# main.net
KiCad netlist of a schematic drawn in Altium Designer
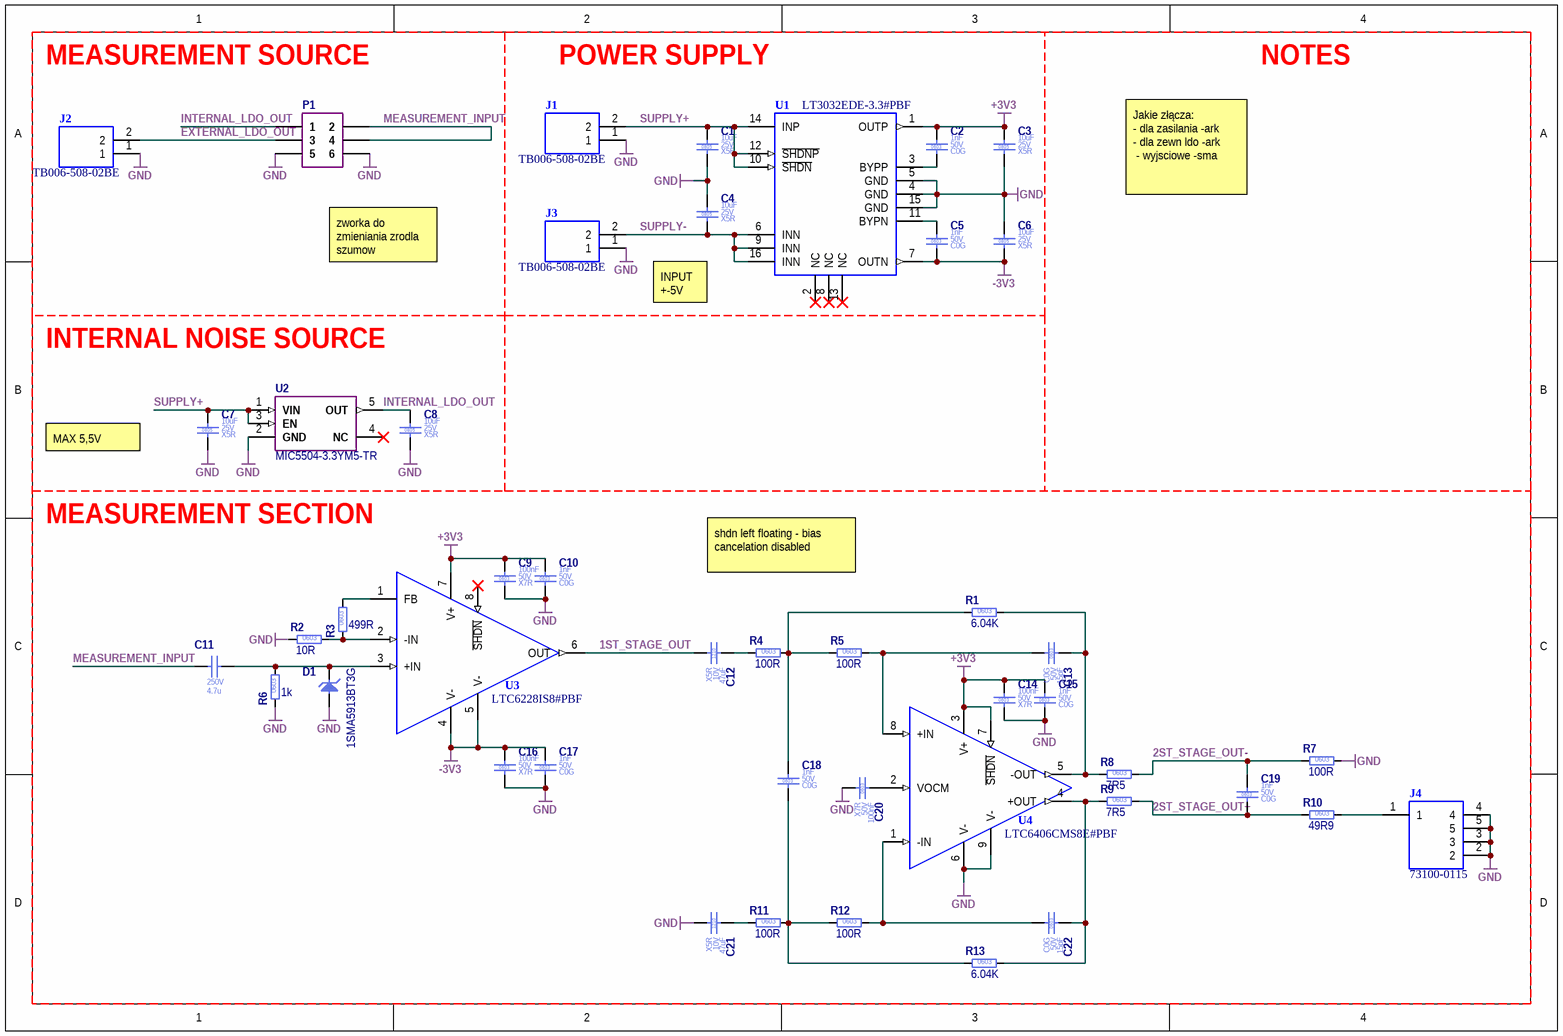
[diagram p0: main.SchDoc]

(export (version "E")
  (design (tool "Eeschema 10.0.6"))
  (components
    (comp (ref "C1")
      (value "C_10UF_25V_X5R_0805_20")
      (footprint "C_0805_2012")
      (description "Ceramic Capacitor")
      (fields
        (field (name "CASE/PACKAGE") "0805")
        (field (name "VOLTAGE RATING (DC)") "25V")
        (field (name "DIELECTRIC") "X5R")
        (field (name "CAPACITANCE") "10uF")
        (field (name "TOLERANCE") "20%")
        (field (name "MANUFACTURER PART NUMBER") "TMK212BBJ106MG-T")
      )
      (libsource (lib "7Sigma") (part "C"))
    )
    (comp (ref "C2")
      (value "C_1NF_50V_C0G_0603_5")
      (footprint "C_0603_1608")
      (description "Ceramic Capacitor")
      (fields
        (field (name "CASE/PACKAGE") "0603")
        (field (name "VOLTAGE RATING (DC)") "50V")
        (field (name "DIELECTRIC") "C0G")
        (field (name "CAPACITANCE") "1nF")
        (field (name "TOLERANCE") "10%")
      )
      (libsource (lib "7Sigma") (part "C"))
    )
    (comp (ref "C3")
      (value "C_10UF_25V_X5R_0805_20")
      (footprint "C_0805_2012")
      (description "Ceramic Capacitor")
      (fields
        (field (name "CASE/PACKAGE") "0805")
        (field (name "VOLTAGE RATING (DC)") "25V")
        (field (name "DIELECTRIC") "X5R")
        (field (name "CAPACITANCE") "10uF")
        (field (name "TOLERANCE") "20%")
        (field (name "MANUFACTURER PART NUMBER") "TMK212BBJ106MG-T")
      )
      (libsource (lib "7Sigma") (part "C"))
    )
    (comp (ref "C4")
      (value "C_10UF_25V_X5R_0805_20")
      (footprint "C_0805_2012")
      (description "Ceramic Capacitor")
      (fields
        (field (name "CASE/PACKAGE") "0805")
        (field (name "VOLTAGE RATING (DC)") "25V")
        (field (name "DIELECTRIC") "X5R")
        (field (name "CAPACITANCE") "10uF")
        (field (name "TOLERANCE") "20%")
        (field (name "MANUFACTURER PART NUMBER") "TMK212BBJ106MG-T")
      )
      (libsource (lib "7Sigma") (part "C"))
    )
    (comp (ref "C5")
      (value "C_1NF_50V_C0G_0603_5")
      (footprint "C_0603_1608")
      (description "Ceramic Capacitor")
      (fields
        (field (name "CASE/PACKAGE") "0603")
        (field (name "VOLTAGE RATING (DC)") "50V")
        (field (name "DIELECTRIC") "C0G")
        (field (name "CAPACITANCE") "1nF")
        (field (name "TOLERANCE") "10%")
      )
      (libsource (lib "7Sigma") (part "C"))
    )
    (comp (ref "C6")
      (value "C_10UF_25V_X5R_0805_20")
      (footprint "C_0805_2012")
      (description "Ceramic Capacitor")
      (fields
        (field (name "CASE/PACKAGE") "0805")
        (field (name "VOLTAGE RATING (DC)") "25V")
        (field (name "DIELECTRIC") "X5R")
        (field (name "CAPACITANCE") "10uF")
        (field (name "TOLERANCE") "20%")
        (field (name "MANUFACTURER PART NUMBER") "TMK212BBJ106MG-T")
      )
      (libsource (lib "7Sigma") (part "C"))
    )
    (comp (ref "C7")
      (value "C_10UF_25V_X5R_0805_20")
      (footprint "C_0805_2012")
      (description "Ceramic Capacitor")
      (fields
        (field (name "CASE/PACKAGE") "0805")
        (field (name "VOLTAGE RATING (DC)") "25V")
        (field (name "DIELECTRIC") "X5R")
        (field (name "CAPACITANCE") "10uF")
        (field (name "TOLERANCE") "20%")
        (field (name "MANUFACTURER PART NUMBER") "TMK212BBJ106MG-T")
      )
      (libsource (lib "7Sigma") (part "C"))
    )
    (comp (ref "C8")
      (value "C_10UF_25V_X5R_0805_20")
      (footprint "C_0805_2012")
      (description "Ceramic Capacitor")
      (fields
        (field (name "CASE/PACKAGE") "0805")
        (field (name "VOLTAGE RATING (DC)") "25V")
        (field (name "DIELECTRIC") "X5R")
        (field (name "CAPACITANCE") "10uF")
        (field (name "TOLERANCE") "20%")
        (field (name "MANUFACTURER PART NUMBER") "TMK212BBJ106MG-T")
      )
      (libsource (lib "7Sigma") (part "C"))
    )
    (comp (ref "C9")
      (value "C_100NF_50V_X7R_0603_5")
      (footprint "C_0603_1608")
      (description "Ceramic Capacitor")
      (fields
        (field (name "CASE/PACKAGE") "0603")
        (field (name "VOLTAGE RATING (DC)") "50V")
        (field (name "DIELECTRIC") "X7R")
        (field (name "CAPACITANCE") "100nF")
        (field (name "TOLERANCE") "5%")
        (field (name "MANUFACTURER PART NUMBER") "CC0603JRX7R9BB104")
      )
      (libsource (lib "7Sigma") (part "C"))
    )
    (comp (ref "C10")
      (value "C_1NF_50V_C0G_0603_5")
      (footprint "C_0603_1608")
      (description "Ceramic Capacitor")
      (fields
        (field (name "CASE/PACKAGE") "0603")
        (field (name "VOLTAGE RATING (DC)") "50V")
        (field (name "DIELECTRIC") "C0G")
        (field (name "CAPACITANCE") "1nF")
        (field (name "TOLERANCE") "10%")
      )
      (libsource (lib "7Sigma") (part "C"))
    )
    (comp (ref "C11")
      (value "C")
      (footprint "CP_22.5mm_tht")
      (description "Film Capacitors 250VDC 4.7uF 10% MPET L/S=22.5mm")
      (fields (field (name "VOLTAGE RATING (DC)") "250V") (field (name "CAPACITANCE") "4.7u"))
      (libsource (lib "SamacSys") (part "CP_4U7_250V_22.5mm_10"))
    )
    (comp (ref "C12")
      (value "C_47UF_10V_X5R_1210_10")
      (footprint "C_1210_3225")
      (description "Ceramic Capacitor")
      (fields
        (field (name "CASE/PACKAGE") "1210")
        (field (name "VOLTAGE RATING (DC)") "10V")
        (field (name "DIELECTRIC") "X5R")
        (field (name "CAPACITANCE") "47uF")
        (field (name "TOLERANCE") "10%")
      )
      (libsource (lib "7Sigma") (part "C"))
    )
    (comp (ref "C13")
      (value "C_15PF_50V_C0G_0603_5")
      (footprint "C_0603_1608")
      (description "Ceramic Capacitor")
      (fields
        (field (name "CASE/PACKAGE") "0603")
        (field (name "VOLTAGE RATING (DC)") "50V")
        (field (name "DIELECTRIC") "C0G")
        (field (name "CAPACITANCE") "15pF")
        (field (name "TOLERANCE") "10%")
      )
      (libsource (lib "7Sigma") (part "C"))
    )
    (comp (ref "C14")
      (value "C_100NF_50V_X7R_0603_5")
      (footprint "C_0603_1608")
      (description "Ceramic Capacitor")
      (fields
        (field (name "CASE/PACKAGE") "0603")
        (field (name "VOLTAGE RATING (DC)") "50V")
        (field (name "DIELECTRIC") "X7R")
        (field (name "CAPACITANCE") "100nF")
        (field (name "TOLERANCE") "5%")
        (field (name "MANUFACTURER PART NUMBER") "CC0603JRX7R9BB104")
      )
      (libsource (lib "7Sigma") (part "C"))
    )
    (comp (ref "C15")
      (value "C_1NF_50V_C0G_0603_5")
      (footprint "C_0603_1608")
      (description "Ceramic Capacitor")
      (fields
        (field (name "CASE/PACKAGE") "0603")
        (field (name "VOLTAGE RATING (DC)") "50V")
        (field (name "DIELECTRIC") "C0G")
        (field (name "CAPACITANCE") "1nF")
        (field (name "TOLERANCE") "10%")
      )
      (libsource (lib "7Sigma") (part "C"))
    )
    (comp (ref "C16")
      (value "C_100NF_50V_X7R_0603_5")
      (footprint "C_0603_1608")
      (description "Ceramic Capacitor")
      (fields
        (field (name "CASE/PACKAGE") "0603")
        (field (name "VOLTAGE RATING (DC)") "50V")
        (field (name "DIELECTRIC") "X7R")
        (field (name "CAPACITANCE") "100nF")
        (field (name "TOLERANCE") "5%")
        (field (name "MANUFACTURER PART NUMBER") "CC0603JRX7R9BB104")
      )
      (libsource (lib "7Sigma") (part "C"))
    )
    (comp (ref "C17")
      (value "C_1NF_50V_C0G_0603_5")
      (footprint "C_0603_1608")
      (description "Ceramic Capacitor")
      (fields
        (field (name "CASE/PACKAGE") "0603")
        (field (name "VOLTAGE RATING (DC)") "50V")
        (field (name "DIELECTRIC") "C0G")
        (field (name "CAPACITANCE") "1nF")
        (field (name "TOLERANCE") "10%")
      )
      (libsource (lib "7Sigma") (part "C"))
    )
    (comp (ref "C18")
      (value "C_1NF_50V_C0G_0603_5")
      (footprint "C_0603_1608")
      (description "Ceramic Capacitor")
      (fields
        (field (name "CASE/PACKAGE") "0603")
        (field (name "VOLTAGE RATING (DC)") "50V")
        (field (name "DIELECTRIC") "C0G")
        (field (name "CAPACITANCE") "1nF")
        (field (name "TOLERANCE") "10%")
      )
      (libsource (lib "7Sigma") (part "C"))
    )
    (comp (ref "C19")
      (value "C_1NF_50V_C0G_0603_5")
      (footprint "C_0603_1608")
      (description "Ceramic Capacitor")
      (fields
        (field (name "CASE/PACKAGE") "0603")
        (field (name "VOLTAGE RATING (DC)") "50V")
        (field (name "DIELECTRIC") "C0G")
        (field (name "CAPACITANCE") "1nF")
        (field (name "TOLERANCE") "10%")
      )
      (libsource (lib "7Sigma") (part "C"))
    )
    (comp (ref "C20")
      (value "C_100NF_50V_X7R_0603_5")
      (footprint "C_0603_1608")
      (description "Ceramic Capacitor")
      (fields
        (field (name "CASE/PACKAGE") "0603")
        (field (name "VOLTAGE RATING (DC)") "50V")
        (field (name "DIELECTRIC") "X7R")
        (field (name "CAPACITANCE") "100nF")
        (field (name "TOLERANCE") "5%")
        (field (name "MANUFACTURER PART NUMBER") "CC0603JRX7R9BB104")
      )
      (libsource (lib "7Sigma") (part "C"))
    )
    (comp (ref "C21")
      (value "C_47UF_10V_X5R_1210_10")
      (footprint "C_1210_3225")
      (description "Ceramic Capacitor")
      (fields
        (field (name "CASE/PACKAGE") "1210")
        (field (name "VOLTAGE RATING (DC)") "10V")
        (field (name "DIELECTRIC") "X5R")
        (field (name "CAPACITANCE") "47uF")
        (field (name "TOLERANCE") "10%")
      )
      (libsource (lib "7Sigma") (part "C"))
    )
    (comp (ref "C22")
      (value "C_15PF_50V_C0G_0603_5")
      (footprint "C_0603_1608")
      (description "Ceramic Capacitor")
      (fields
        (field (name "CASE/PACKAGE") "0603")
        (field (name "VOLTAGE RATING (DC)") "50V")
        (field (name "DIELECTRIC") "C0G")
        (field (name "CAPACITANCE") "15pF")
        (field (name "TOLERANCE") "10%")
      )
      (libsource (lib "7Sigma") (part "C"))
    )
    (comp (ref "D1")
      (value "1SMA5913BT3G")
      (footprint "SMA-2")
      (description "Zener Diodes 3.3V 1.5W")
      (libsource (lib "SamacSys") (part "1SMA5913BT3G"))
    )
    (comp (ref "J1")
      (value "TB006-508-02BE")
      (footprint "SamacSys:TB00650802BE")
      (fields (field (name "MOUSER PART NUMBER") "490-TB006-508-02BE"))
      (libsource (lib "SamacSys") (part "TB006-508-02BE"))
    )
    (comp (ref "J2")
      (value "TB006-508-02BE")
      (footprint "SamacSys:TB00650802BE")
      (fields (field (name "MOUSER PART NUMBER") "490-TB006-508-02BE"))
      (libsource (lib "SamacSys") (part "TB006-508-02BE"))
    )
    (comp (ref "J3")
      (value "TB006-508-02BE")
      (footprint "SamacSys:TB00650802BE")
      (fields (field (name "MOUSER PART NUMBER") "490-TB006-508-02BE"))
      (libsource (lib "SamacSys") (part "TB006-508-02BE"))
    )
    (comp (ref "J4")
      (value "73100-0115")
      (footprint "SamacSys:731000115")
      (description "SMA right angle connector female")
      (fields (field (name "MOUSER PART NUMBER") "538-73100-0115"))
      (libsource (lib "SamacSys") (part "73100-0115"))
    )
    (comp (ref "P1")
      (value "826925-3")
      (footprint "HEADER_M_2x3_2.54")
      (description "Header, 3-Pin, Dual row")
      (fields (field (name "MANUFACTURER") "TE Connectivity"))
      (libsource (lib "7Sigma") (part "HEADER_2x3"))
    )
    (comp (ref "R1")
      (value "R_6K04_0603_1")
      (footprint "R_0603_1608")
      (description "Thin Film Resistor")
      (fields
        (field (name "RESISTANCE") "6.04K")
        (field (name "CASE/PACKAGE") "0603")
        (field (name "TOLERANCE") "1%")
        (field (name "MANUFACTURER") "Yageo")
      )
      (libsource (lib "7Sigma") (part "R"))
    )
    (comp (ref "R2")
      (value "R_10R_0603_1")
      (footprint "R_0603_1608")
      (fields
        (field (name "RESISTANCE") "10R")
        (field (name "CASE/PACKAGE") "0603")
        (field (name "TOLERANCE") "1%")
      )
      (libsource (lib "7Sigma") (part "R"))
    )
    (comp (ref "R3")
      (value "R_499R_0603_1")
      (footprint "R_0603_1608")
      (description "Thin Film Resistors")
      (fields
        (field (name "RESISTANCE") "499R")
        (field (name "CASE/PACKAGE") "0603")
        (field (name "TOLERANCE") "1%")
        (field (name "MANUFACTURER") "Yageo")
      )
      (libsource (lib "7Sigma") (part "R"))
    )
    (comp (ref "R4")
      (value "R_100R_0603_1")
      (footprint "R_0603_1608")
      (fields
        (field (name "RESISTANCE") "100R")
        (field (name "CASE/PACKAGE") "0603")
        (field (name "TOLERANCE") "1%")
      )
      (libsource (lib "7Sigma") (part "R"))
    )
    (comp (ref "R5")
      (value "R_100R_0603_1")
      (footprint "R_0603_1608")
      (fields
        (field (name "RESISTANCE") "100R")
        (field (name "CASE/PACKAGE") "0603")
        (field (name "TOLERANCE") "1%")
      )
      (libsource (lib "7Sigma") (part "R"))
    )
    (comp (ref "R6")
      (value "R_1K_0603_1")
      (footprint "R_0603_1608")
      (fields
        (field (name "RESISTANCE") "1k")
        (field (name "CASE/PACKAGE") "0603")
        (field (name "TOLERANCE") "1%")
      )
      (libsource (lib "7Sigma") (part "R"))
    )
    (comp (ref "R7")
      (value "R_100R_0603_1")
      (footprint "R_0603_1608")
      (fields
        (field (name "RESISTANCE") "100R")
        (field (name "CASE/PACKAGE") "0603")
        (field (name "TOLERANCE") "1%")
      )
      (libsource (lib "7Sigma") (part "R"))
    )
    (comp (ref "R8")
      (value "R_7R5_0603_1")
      (footprint "R_0603_1608")
      (description "Thin Film Resistor")
      (fields
        (field (name "RESISTANCE") "7R5")
        (field (name "CASE/PACKAGE") "0603")
        (field (name "TOLERANCE") "1%")
        (field (name "MANUFACTURER") "Yageo")
      )
      (libsource (lib "7Sigma") (part "R"))
    )
    (comp (ref "R9")
      (value "R_7R5_0603_1")
      (footprint "R_0603_1608")
      (description "Thin Film Resistor")
      (fields
        (field (name "RESISTANCE") "7R5")
        (field (name "CASE/PACKAGE") "0603")
        (field (name "TOLERANCE") "1%")
        (field (name "MANUFACTURER") "Yageo")
      )
      (libsource (lib "7Sigma") (part "R"))
    )
    (comp (ref "R10")
      (value "R_49R9_0603_1")
      (footprint "R_0603_1608")
      (description "Thin Film Resistors")
      (fields
        (field (name "RESISTANCE") "49R9")
        (field (name "CASE/PACKAGE") "0603")
        (field (name "TOLERANCE") "1%")
        (field (name "MANUFACTURER") "Yageo")
      )
      (libsource (lib "7Sigma") (part "R"))
    )
    (comp (ref "R11")
      (value "R_100R_0603_1")
      (footprint "R_0603_1608")
      (fields
        (field (name "RESISTANCE") "100R")
        (field (name "CASE/PACKAGE") "0603")
        (field (name "TOLERANCE") "1%")
      )
      (libsource (lib "7Sigma") (part "R"))
    )
    (comp (ref "R12")
      (value "R_100R_0603_1")
      (footprint "R_0603_1608")
      (fields
        (field (name "RESISTANCE") "100R")
        (field (name "CASE/PACKAGE") "0603")
        (field (name "TOLERANCE") "1%")
      )
      (libsource (lib "7Sigma") (part "R"))
    )
    (comp (ref "R13")
      (value "R_6K04_0603_1")
      (footprint "R_0603_1608")
      (description "Thin Film Resistor")
      (fields
        (field (name "RESISTANCE") "6.04K")
        (field (name "CASE/PACKAGE") "0603")
        (field (name "TOLERANCE") "1%")
        (field (name "MANUFACTURER") "Yageo")
      )
      (libsource (lib "7Sigma") (part "R"))
    )
    (comp (ref "U1")
      (value "LT3032EDE-3.3#PBF")
      (footprint "SamacSys:LT3032EDE5PBF")
      (fields (field (name "MOUSER PART NUMBER") "584-LT3032EDE-3.3PBF"))
      (libsource (lib "SamacSys") (part "LT3032EDE-5#PBF"))
    )
    (comp (ref "U2")
      (value "MIC5504-3.3YM5-TR")
      (footprint "SOT23-5_SC74A_SOT753_M")
      (description "LDO Voltage Regulators Single 300mA LDO")
      (fields (field (name "MANUFACTURER") "Microchip"))
      (libsource (lib "7Sigma") (part "MIC5504-3.3YM5-TR"))
    )
    (comp (ref "U3")
      (value "LTC6228IS8#PBF")
      (footprint "SamacSys:SOIC127P599X175-8N")
      (description "High Speed Operational Amplifiers Precision Low Drift & Noise HiSpeed")
      (fields (field (name "MOUSER PART NUMBER") "584-LTC6228IS8#PBF"))
      (libsource (lib "SamacSys") (part "LTC6228IS8#PBF"))
    )
    (comp (ref "U4")
      (value "LTC6406CMS8E#PBF")
      (footprint "SamacSys:SOP65P490X110-9N")
      (fields (field (name "MOUSER PART NUMBER") "584-LTC6406CMS8E#PBF"))
      (libsource (lib "SamacSys") (part "LTC6406CMS8E#PBF"))
    )
  )
  (nets
    (net (code "1") (name "+3V3") (class "Default")
      (node (ref "C10") (pin "1") (pinfunction "1_1") (pintype "passive"))
      (node (ref "C14") (pin "1") (pinfunction "1_1") (pintype "passive"))
      (node (ref "C15") (pin "1") (pinfunction "1_1") (pintype "passive"))
      (node (ref "C2") (pin "1") (pinfunction "1_1") (pintype "passive"))
      (node (ref "C3") (pin "1") (pinfunction "1_1") (pintype "passive"))
      (node (ref "C9") (pin "1") (pinfunction "1_1") (pintype "passive"))
      (node (ref "U1") (pin "1") (pinfunction "OUTP_1") (pintype "output"))
      (node (ref "U3") (pin "7") (pinfunction "V+_7") (pintype "power_in"))
      (node (ref "U4") (pin "3") (pinfunction "V+_3") (pintype "power_in"))
      (node (ref "U4") (pin "7") (pinfunction "~{SHDN}_7") (pintype "input"))
    )
    (net (code "2") (name "-3V3") (class "Default")
      (node (ref "C16") (pin "1") (pinfunction "1_1") (pintype "passive"))
      (node (ref "C17") (pin "1") (pinfunction "1_1") (pintype "passive"))
      (node (ref "C5") (pin "2") (pinfunction "2_2") (pintype "passive"))
      (node (ref "C6") (pin "2") (pinfunction "2_2") (pintype "passive"))
      (node (ref "U1") (pin "7") (pinfunction "OUTN_7") (pintype "output"))
      (node (ref "U3") (pin "4") (pinfunction "V-_4") (pintype "power_in"))
      (node (ref "U3") (pin "5") (pinfunction "V-_5") (pintype "power_in"))
    )
    (net (code "3") (name "/1ST_STAGE_OUT") (class "Default")
      (node (ref "C12") (pin "2") (pinfunction "2_2") (pintype "passive"))
      (node (ref "U3") (pin "6") (pinfunction "OUT_6") (pintype "output"))
    )
    (net (code "4") (name "/2ST_STAGE_OUT+") (class "Default")
      (node (ref "C19") (pin "2") (pinfunction "2_2") (pintype "passive"))
      (node (ref "R10") (pin "1") (pinfunction "1_1") (pintype "passive"))
      (node (ref "R9") (pin "2") (pinfunction "2_2") (pintype "passive"))
    )
    (net (code "5") (name "/2ST_STAGE_OUT-") (class "Default")
      (node (ref "C19") (pin "1") (pinfunction "1_1") (pintype "passive"))
      (node (ref "R7") (pin "1") (pinfunction "1_1") (pintype "passive"))
      (node (ref "R8") (pin "2") (pinfunction "2_2") (pintype "passive"))
    )
    (net (code "6") (name "/EXTERNAL_LDO_OUT") (class "Default")
      (node (ref "J2") (pin "2") (pinfunction "2_2") (pintype "passive"))
      (node (ref "P1") (pin "3") (pinfunction "3_3") (pintype "passive"))
    )
    (net (code "7") (name "/INTERNAL_LDO_OUT") (class "Default")
      (node (ref "C8") (pin "1") (pinfunction "1_1") (pintype "passive"))
      (node (ref "P1") (pin "1") (pinfunction "1_1") (pintype "passive"))
      (node (ref "U2") (pin "5") (pinfunction "OUT_5") (pintype "output"))
    )
    (net (code "8") (name "/MEASUREMENT_INPUT") (class "Default")
      (node (ref "C11") (pin "2") (pinfunction "2_2") (pintype "passive"))
      (node (ref "P1") (pin "2") (pinfunction "2_2") (pintype "passive"))
      (node (ref "P1") (pin "4") (pinfunction "4_4") (pintype "passive"))
    )
    (net (code "9") (name "/SUPPLY+") (class "Default")
      (node (ref "C1") (pin "1") (pinfunction "1_1") (pintype "passive"))
      (node (ref "C7") (pin "1") (pinfunction "1_1") (pintype "passive"))
      (node (ref "J1") (pin "2") (pinfunction "2_2") (pintype "passive"))
      (node (ref "U1") (pin "10") (pinfunction "~{SHDN}_10") (pintype "input"))
      (node (ref "U1") (pin "12") (pinfunction "~{SHDNP}_12") (pintype "input"))
      (node (ref "U1") (pin "14") (pinfunction "INP_14") (pintype "power_in"))
      (node (ref "U2") (pin "1") (pinfunction "VIN_1") (pintype "input"))
      (node (ref "U2") (pin "3") (pinfunction "EN_3") (pintype "input"))
    )
    (net (code "10") (name "/SUPPLY-") (class "Default")
      (node (ref "C4") (pin "2") (pinfunction "2_2") (pintype "passive"))
      (node (ref "J3") (pin "2") (pinfunction "2_2") (pintype "passive"))
      (node (ref "U1") (pin "16") (pinfunction "INN_16") (pintype "power_in"))
      (node (ref "U1") (pin "6") (pinfunction "INN_6") (pintype "power_in"))
      (node (ref "U1") (pin "9") (pinfunction "INN_9") (pintype "power_in"))
    )
    (net (code "11") (name "GND") (class "Default")
      (node (ref "C1") (pin "2") (pinfunction "2_2") (pintype "passive"))
      (node (ref "C10") (pin "2") (pinfunction "2_2") (pintype "passive"))
      (node (ref "C14") (pin "2") (pinfunction "2_2") (pintype "passive"))
      (node (ref "C15") (pin "2") (pinfunction "2_2") (pintype "passive"))
      (node (ref "C16") (pin "2") (pinfunction "2_2") (pintype "passive"))
      (node (ref "C17") (pin "2") (pinfunction "2_2") (pintype "passive"))
      (node (ref "C20") (pin "2") (pinfunction "2_2") (pintype "passive"))
      (node (ref "C21") (pin "2") (pinfunction "2_2") (pintype "passive"))
      (node (ref "C3") (pin "2") (pinfunction "2_2") (pintype "passive"))
      (node (ref "C4") (pin "1") (pinfunction "1_1") (pintype "passive"))
      (node (ref "C6") (pin "1") (pinfunction "1_1") (pintype "passive"))
      (node (ref "C7") (pin "2") (pinfunction "2_2") (pintype "passive"))
      (node (ref "C8") (pin "2") (pinfunction "2_2") (pintype "passive"))
      (node (ref "C9") (pin "2") (pinfunction "2_2") (pintype "passive"))
      (node (ref "D1") (pin "1") (pinfunction "A_1") (pintype "passive"))
      (node (ref "J1") (pin "1") (pinfunction "1_1") (pintype "passive"))
      (node (ref "J2") (pin "1") (pinfunction "1_1") (pintype "passive"))
      (node (ref "J3") (pin "1") (pinfunction "1_1") (pintype "passive"))
      (node (ref "J4") (pin "2") (pinfunction "2_2") (pintype "passive"))
      (node (ref "J4") (pin "3") (pinfunction "3_3") (pintype "passive"))
      (node (ref "J4") (pin "4") (pinfunction "4_4") (pintype "passive"))
      (node (ref "J4") (pin "5") (pinfunction "5_5") (pintype "passive"))
      (node (ref "P1") (pin "5") (pinfunction "5_5") (pintype "passive"))
      (node (ref "P1") (pin "6") (pinfunction "6_6") (pintype "passive"))
      (node (ref "R2") (pin "1") (pinfunction "1_1") (pintype "passive"))
      (node (ref "R6") (pin "1") (pinfunction "1_1") (pintype "passive"))
      (node (ref "R7") (pin "2") (pinfunction "2_2") (pintype "passive"))
      (node (ref "U1") (pin "15") (pinfunction "GND_15") (pintype "power_in"))
      (node (ref "U1") (pin "4") (pinfunction "GND_4") (pintype "power_in"))
      (node (ref "U1") (pin "5") (pinfunction "GND_5") (pintype "power_in"))
      (node (ref "U2") (pin "2") (pinfunction "GND_2") (pintype "power_in"))
      (node (ref "U4") (pin "6") (pinfunction "V-_6") (pintype "power_in"))
      (node (ref "U4") (pin "9") (pinfunction "V-_9") (pintype "power_in"))
    )
    (net (code "12") (name "Net-(C12-Pad1)") (class "Default")
      (node (ref "C12") (pin "1") (pinfunction "1_1") (pintype "passive"))
      (node (ref "R4") (pin "1") (pinfunction "1_1") (pintype "passive"))
    )
    (net (code "13") (name "Net-(C18-Pad1)") (class "Default")
      (node (ref "C18") (pin "1") (pinfunction "1_1") (pintype "passive"))
      (node (ref "R1") (pin "1") (pinfunction "1_1") (pintype "passive"))
      (node (ref "R4") (pin "2") (pinfunction "2_2") (pintype "passive"))
      (node (ref "R5") (pin "1") (pinfunction "1_1") (pintype "passive"))
    )
    (net (code "14") (name "Net-(C18-Pad2)") (class "Default")
      (node (ref "C18") (pin "2") (pinfunction "2_2") (pintype "passive"))
      (node (ref "R11") (pin "2") (pinfunction "2_2") (pintype "passive"))
      (node (ref "R12") (pin "1") (pinfunction "1_1") (pintype "passive"))
      (node (ref "R13") (pin "1") (pinfunction "1_1") (pintype "passive"))
    )
    (net (code "15") (name "Net-(C21-Pad1)") (class "Default")
      (node (ref "C21") (pin "1") (pinfunction "1_1") (pintype "passive"))
      (node (ref "R11") (pin "1") (pinfunction "1_1") (pintype "passive"))
    )
    (net (code "16") (name "Net-(D1-C)") (class "Default")
      (node (ref "C11") (pin "1") (pinfunction "1_1") (pintype "passive"))
      (node (ref "D1") (pin "2") (pinfunction "C_2") (pintype "passive"))
      (node (ref "R6") (pin "2") (pinfunction "2_2") (pintype "passive"))
      (node (ref "U3") (pin "3") (pinfunction "+IN_3") (pintype "input"))
    )
    (net (code "17") (name "Net-(J4-Pad1)") (class "Default")
      (node (ref "J4") (pin "1") (pinfunction "1_1") (pintype "passive"))
      (node (ref "R10") (pin "2") (pinfunction "2_2") (pintype "passive"))
    )
    (net (code "18") (name "Net-(U1-BYPN)") (class "Default")
      (node (ref "C5") (pin "1") (pinfunction "1_1") (pintype "passive"))
      (node (ref "U1") (pin "11") (pinfunction "BYPN_11") (pintype "passive"))
    )
    (net (code "19") (name "Net-(U1-BYPP)") (class "Default")
      (node (ref "C2") (pin "2") (pinfunction "2_2") (pintype "passive"))
      (node (ref "U1") (pin "3") (pinfunction "BYPP_3") (pintype "passive"))
    )
    (net (code "20") (name "Net-(U3--IN)") (class "Default")
      (node (ref "R2") (pin "2") (pinfunction "2_2") (pintype "passive"))
      (node (ref "R3") (pin "1") (pinfunction "1_1") (pintype "passive"))
      (node (ref "U3") (pin "2") (pinfunction "-IN_2") (pintype "input"))
    )
    (net (code "21") (name "Net-(U3-FB)") (class "Default")
      (node (ref "R3") (pin "2") (pinfunction "2_2") (pintype "passive"))
      (node (ref "U3") (pin "1") (pinfunction "FB_1") (pintype "passive"))
    )
    (net (code "22") (name "Net-(U4-+IN)") (class "Default")
      (node (ref "C13") (pin "2") (pinfunction "2_2") (pintype "passive"))
      (node (ref "R5") (pin "2") (pinfunction "2_2") (pintype "passive"))
      (node (ref "U4") (pin "8") (pinfunction "+IN_8") (pintype "input"))
    )
    (net (code "23") (name "Net-(U4-+OUT)") (class "Default")
      (node (ref "C22") (pin "1") (pinfunction "1_1") (pintype "passive"))
      (node (ref "R13") (pin "2") (pinfunction "2_2") (pintype "passive"))
      (node (ref "R9") (pin "1") (pinfunction "1_1") (pintype "passive"))
      (node (ref "U4") (pin "4") (pinfunction "+OUT_4") (pintype "output"))
    )
    (net (code "24") (name "Net-(U4--IN)") (class "Default")
      (node (ref "C22") (pin "2") (pinfunction "2_2") (pintype "passive"))
      (node (ref "R12") (pin "2") (pinfunction "2_2") (pintype "passive"))
      (node (ref "U4") (pin "1") (pinfunction "-IN_1") (pintype "input"))
    )
    (net (code "25") (name "Net-(U4--OUT)") (class "Default")
      (node (ref "C13") (pin "1") (pinfunction "1_1") (pintype "passive"))
      (node (ref "R1") (pin "2") (pinfunction "2_2") (pintype "passive"))
      (node (ref "R8") (pin "1") (pinfunction "1_1") (pintype "passive"))
      (node (ref "U4") (pin "5") (pinfunction "-OUT_5") (pintype "output"))
    )
    (net (code "26") (name "Net-(U4-VOCM)") (class "Default")
      (node (ref "C20") (pin "1") (pinfunction "1_1") (pintype "passive"))
      (node (ref "U4") (pin "2") (pinfunction "VOCM_2") (pintype "input"))
    )
    (net (code "27") (name "unconnected-(U1-NC-Pad2)") (class "Default")
      (node (ref "U1") (pin "2") (pinfunction "NC_2") (pintype "passive+no_connect"))
    )
    (net (code "28") (name "unconnected-(U1-NC-Pad8)") (class "Default")
      (node (ref "U1") (pin "8") (pinfunction "NC_8") (pintype "passive+no_connect"))
    )
    (net (code "29") (name "unconnected-(U1-NC-Pad13)") (class "Default")
      (node (ref "U1") (pin "13") (pinfunction "NC_13") (pintype "passive+no_connect"))
    )
    (net (code "30") (name "unconnected-(U2-NC-Pad4)") (class "Default")
      (node (ref "U2") (pin "4") (pinfunction "NC_4") (pintype "passive+no_connect"))
    )
    (net (code "31") (name "unconnected-(U3-~{SHDN}-Pad8)") (class "Default")
      (node (ref "U3") (pin "8") (pinfunction "~{SHDN}_8") (pintype "input+no_connect"))
    )
  )
)
